# due-adaptor-sanguinololu-end.net
KiCad netlist of a schematic drawn in EAGLE
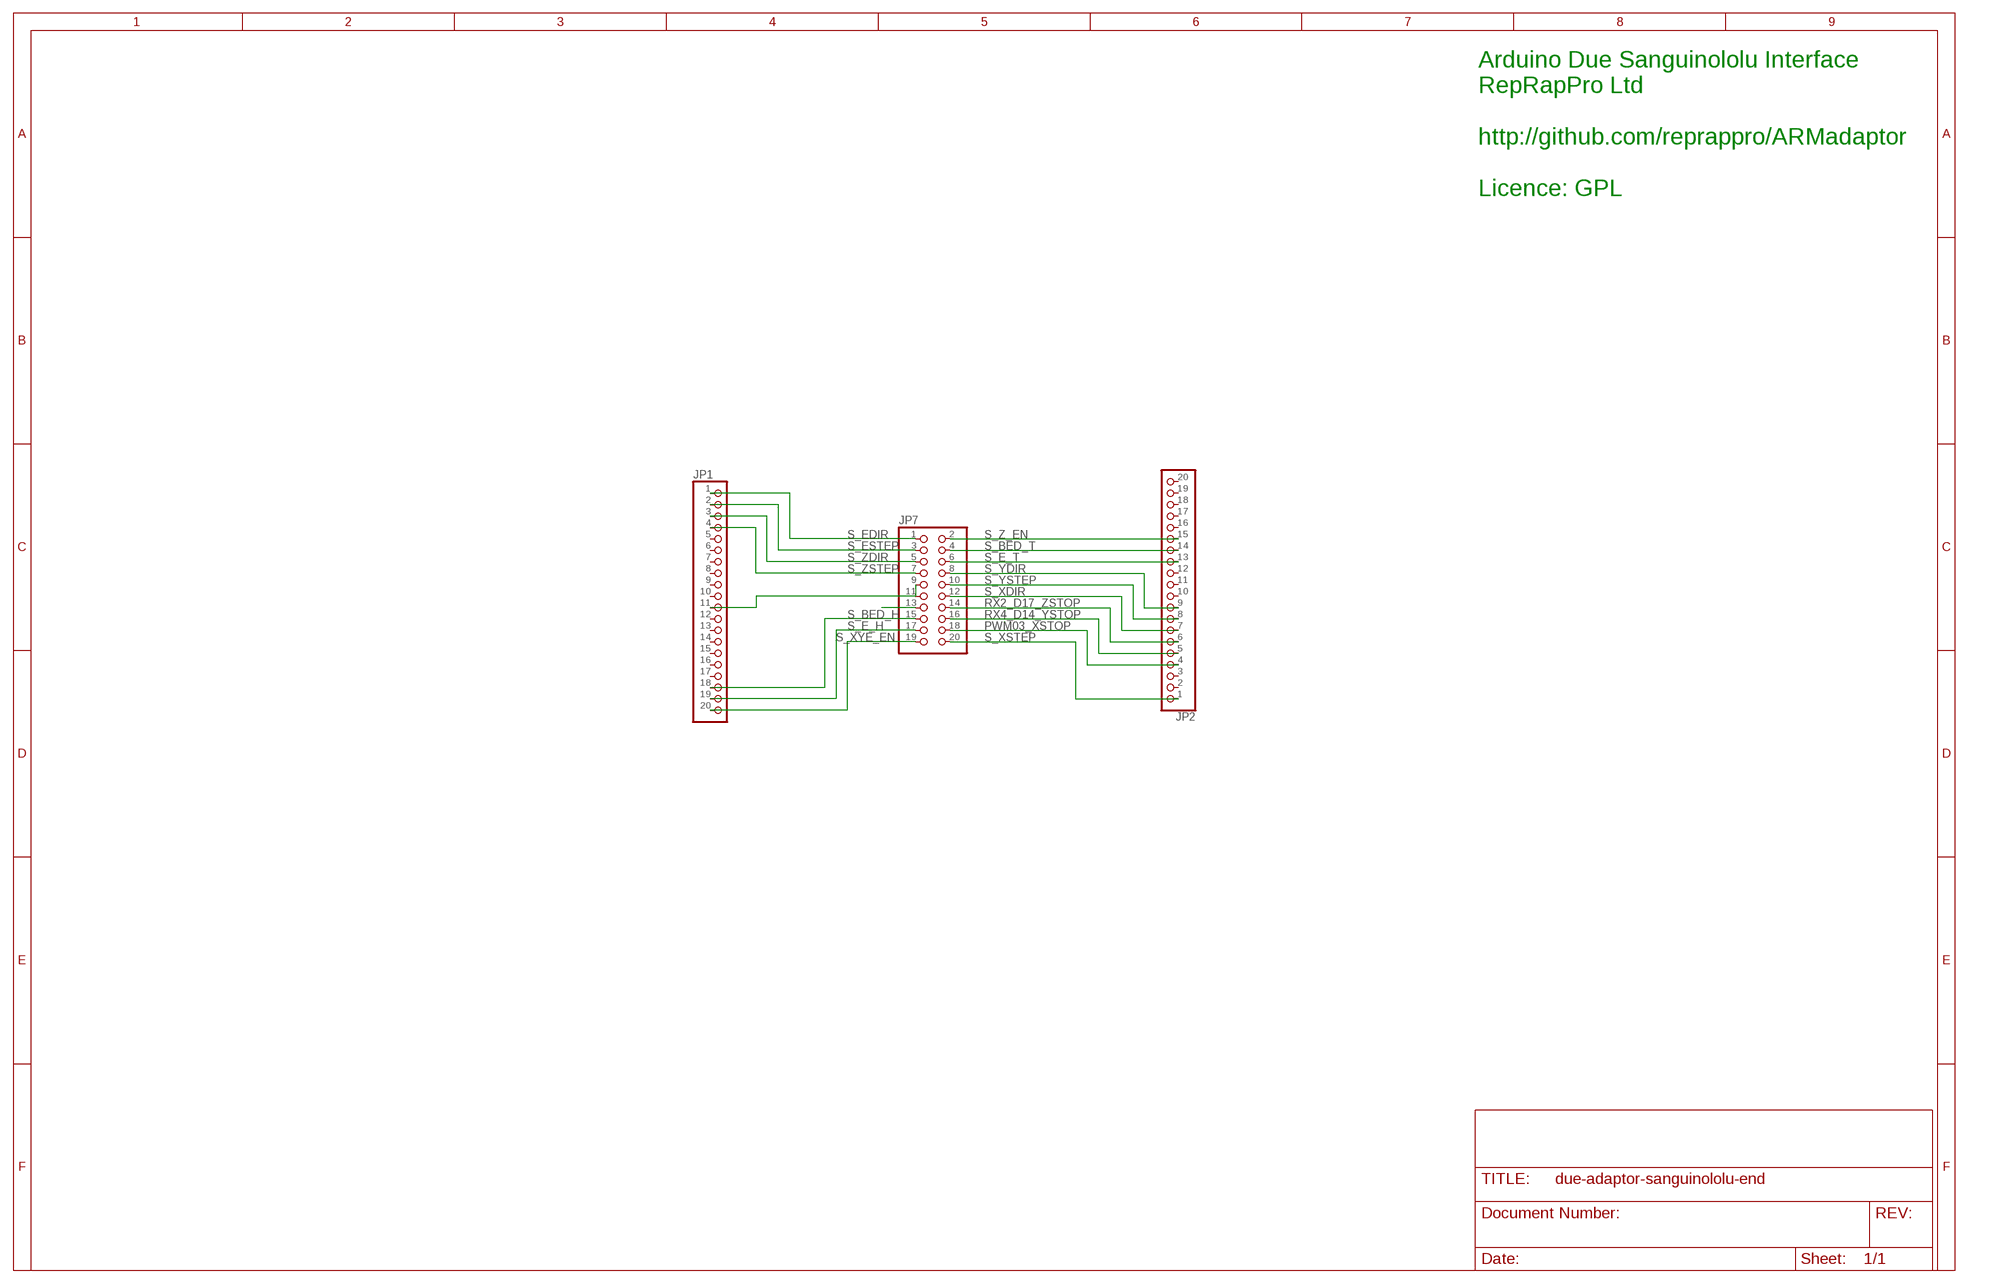
[diagram p0: schematic, sheet 1]

(export (version "E")
  (design (tool "Eeschema 10.0.6"))
  (components
    (comp (ref "JP1")
      (value "PINHD-1X20")
      (footprint "eagle-import:1X20")
      (libsource (lib "eagle-import") (part "PINHD-1X20"))
    )
    (comp (ref "JP2")
      (value "PINHD-1X20")
      (footprint "eagle-import:1X20")
      (libsource (lib "eagle-import") (part "PINHD-1X20"))
    )
    (comp (ref "JP7")
      (value "PINHD-2X10")
      (footprint "eagle-import:2X10")
      (libsource (lib "eagle-import") (part "PINHD-2X10"))
    )
  )
  (nets
    (net (code "1") (name "/PWM03_XSTOP") (class "Default")
      (node (ref "JP2") (pin "4") (pinfunction "4_4") (pintype "passive"))
      (node (ref "JP7") (pin "18") (pinfunction "18_18") (pintype "passive"))
    )
    (net (code "2") (name "/RX2_D17_ZSTOP") (class "Default")
      (node (ref "JP2") (pin "6") (pinfunction "6_6") (pintype "passive"))
      (node (ref "JP7") (pin "14") (pinfunction "14_14") (pintype "passive"))
    )
    (net (code "3") (name "/RX4_D14_YSTOP") (class "Default")
      (node (ref "JP2") (pin "5") (pinfunction "5_5") (pintype "passive"))
      (node (ref "JP7") (pin "16") (pinfunction "16_16") (pintype "passive"))
    )
    (net (code "4") (name "/S_BED_H") (class "Default")
      (node (ref "JP1") (pin "18") (pinfunction "18_18") (pintype "passive"))
      (node (ref "JP7") (pin "15") (pinfunction "15_15") (pintype "passive"))
    )
    (net (code "5") (name "/S_BED_T") (class "Default")
      (node (ref "JP2") (pin "14") (pinfunction "14_14") (pintype "passive"))
      (node (ref "JP7") (pin "4") (pinfunction "4_4") (pintype "passive"))
    )
    (net (code "6") (name "/S_EDIR") (class "Default")
      (node (ref "JP1") (pin "1") (pinfunction "1_1") (pintype "passive"))
      (node (ref "JP7") (pin "1") (pinfunction "1_1") (pintype "passive"))
    )
    (net (code "7") (name "/S_ESTEP") (class "Default")
      (node (ref "JP1") (pin "2") (pinfunction "2_2") (pintype "passive"))
      (node (ref "JP7") (pin "3") (pinfunction "3_3") (pintype "passive"))
    )
    (net (code "8") (name "/S_E_H") (class "Default")
      (node (ref "JP1") (pin "19") (pinfunction "19_19") (pintype "passive"))
      (node (ref "JP7") (pin "17") (pinfunction "17_17") (pintype "passive"))
    )
    (net (code "9") (name "/S_E_T") (class "Default")
      (node (ref "JP2") (pin "13") (pinfunction "13_13") (pintype "passive"))
      (node (ref "JP7") (pin "6") (pinfunction "6_6") (pintype "passive"))
    )
    (net (code "10") (name "/S_XDIR") (class "Default")
      (node (ref "JP2") (pin "7") (pinfunction "7_7") (pintype "passive"))
      (node (ref "JP7") (pin "12") (pinfunction "12_12") (pintype "passive"))
    )
    (net (code "11") (name "/S_XSTEP") (class "Default")
      (node (ref "JP2") (pin "1") (pinfunction "1_1") (pintype "passive"))
      (node (ref "JP7") (pin "20") (pinfunction "20_20") (pintype "passive"))
    )
    (net (code "12") (name "/S_XYE_EN") (class "Default")
      (node (ref "JP1") (pin "20") (pinfunction "20_20") (pintype "passive"))
      (node (ref "JP7") (pin "19") (pinfunction "19_19") (pintype "passive"))
    )
    (net (code "13") (name "/S_YDIR") (class "Default")
      (node (ref "JP2") (pin "9") (pinfunction "9_9") (pintype "passive"))
      (node (ref "JP7") (pin "8") (pinfunction "8_8") (pintype "passive"))
    )
    (net (code "14") (name "/S_YSTEP") (class "Default")
      (node (ref "JP2") (pin "8") (pinfunction "8_8") (pintype "passive"))
      (node (ref "JP7") (pin "10") (pinfunction "10_10") (pintype "passive"))
    )
    (net (code "15") (name "/S_ZDIR") (class "Default")
      (node (ref "JP1") (pin "3") (pinfunction "3_3") (pintype "passive"))
      (node (ref "JP7") (pin "5") (pinfunction "5_5") (pintype "passive"))
    )
    (net (code "16") (name "/S_ZSTEP") (class "Default")
      (node (ref "JP1") (pin "4") (pinfunction "4_4") (pintype "passive"))
      (node (ref "JP7") (pin "7") (pinfunction "7_7") (pintype "passive"))
    )
    (net (code "17") (name "/S_Z_EN") (class "Default")
      (node (ref "JP2") (pin "15") (pinfunction "15_15") (pintype "passive"))
      (node (ref "JP7") (pin "2") (pinfunction "2_2") (pintype "passive"))
    )
    (net (code "18") (name "Net-(JP1-Pad11)") (class "Default")
      (node (ref "JP1") (pin "11") (pinfunction "11_11") (pintype "passive"))
      (node (ref "JP7") (pin "11") (pinfunction "11_11") (pintype "passive"))
      (node (ref "JP7") (pin "9") (pinfunction "9_9") (pintype "passive"))
    )
    (net (code "19") (name "unconnected-(JP1-Pad5)") (class "Default")
      (node (ref "JP1") (pin "5") (pinfunction "5_5") (pintype "passive"))
    )
    (net (code "20") (name "unconnected-(JP1-Pad6)") (class "Default")
      (node (ref "JP1") (pin "6") (pinfunction "6_6") (pintype "passive"))
    )
    (net (code "21") (name "unconnected-(JP1-Pad7)") (class "Default")
      (node (ref "JP1") (pin "7") (pinfunction "7_7") (pintype "passive"))
    )
    (net (code "22") (name "unconnected-(JP1-Pad8)") (class "Default")
      (node (ref "JP1") (pin "8") (pinfunction "8_8") (pintype "passive"))
    )
    (net (code "23") (name "unconnected-(JP1-Pad9)") (class "Default")
      (node (ref "JP1") (pin "9") (pinfunction "9_9") (pintype "passive"))
    )
    (net (code "24") (name "unconnected-(JP1-Pad10)") (class "Default")
      (node (ref "JP1") (pin "10") (pinfunction "10_10") (pintype "passive"))
    )
    (net (code "25") (name "unconnected-(JP1-Pad12)") (class "Default")
      (node (ref "JP1") (pin "12") (pinfunction "12_12") (pintype "passive"))
    )
    (net (code "26") (name "unconnected-(JP1-Pad13)") (class "Default")
      (node (ref "JP1") (pin "13") (pinfunction "13_13") (pintype "passive"))
    )
    (net (code "27") (name "unconnected-(JP1-Pad14)") (class "Default")
      (node (ref "JP1") (pin "14") (pinfunction "14_14") (pintype "passive"))
    )
    (net (code "28") (name "unconnected-(JP1-Pad15)") (class "Default")
      (node (ref "JP1") (pin "15") (pinfunction "15_15") (pintype "passive"))
    )
    (net (code "29") (name "unconnected-(JP1-Pad16)") (class "Default")
      (node (ref "JP1") (pin "16") (pinfunction "16_16") (pintype "passive"))
    )
    (net (code "30") (name "unconnected-(JP1-Pad17)") (class "Default")
      (node (ref "JP1") (pin "17") (pinfunction "17_17") (pintype "passive"))
    )
    (net (code "31") (name "unconnected-(JP2-Pad2)") (class "Default")
      (node (ref "JP2") (pin "2") (pinfunction "2_2") (pintype "passive"))
    )
    (net (code "32") (name "unconnected-(JP2-Pad3)") (class "Default")
      (node (ref "JP2") (pin "3") (pinfunction "3_3") (pintype "passive"))
    )
    (net (code "33") (name "unconnected-(JP2-Pad10)") (class "Default")
      (node (ref "JP2") (pin "10") (pinfunction "10_10") (pintype "passive"))
    )
    (net (code "34") (name "unconnected-(JP2-Pad11)") (class "Default")
      (node (ref "JP2") (pin "11") (pinfunction "11_11") (pintype "passive"))
    )
    (net (code "35") (name "unconnected-(JP2-Pad12)") (class "Default")
      (node (ref "JP2") (pin "12") (pinfunction "12_12") (pintype "passive"))
    )
    (net (code "36") (name "unconnected-(JP2-Pad16)") (class "Default")
      (node (ref "JP2") (pin "16") (pinfunction "16_16") (pintype "passive"))
    )
    (net (code "37") (name "unconnected-(JP2-Pad17)") (class "Default")
      (node (ref "JP2") (pin "17") (pinfunction "17_17") (pintype "passive"))
    )
    (net (code "38") (name "unconnected-(JP2-Pad18)") (class "Default")
      (node (ref "JP2") (pin "18") (pinfunction "18_18") (pintype "passive"))
    )
    (net (code "39") (name "unconnected-(JP2-Pad19)") (class "Default")
      (node (ref "JP2") (pin "19") (pinfunction "19_19") (pintype "passive"))
    )
    (net (code "40") (name "unconnected-(JP2-Pad20)") (class "Default")
      (node (ref "JP2") (pin "20") (pinfunction "20_20") (pintype "passive"))
    )
    (net (code "41") (name "unconnected-(JP7-Pad13)") (class "Default")
      (node (ref "JP7") (pin "13") (pinfunction "13_13") (pintype "passive"))
    )
  )
)
